# SCH_GPS.net
KiCad netlist of a schematic drawn in EasyEDA
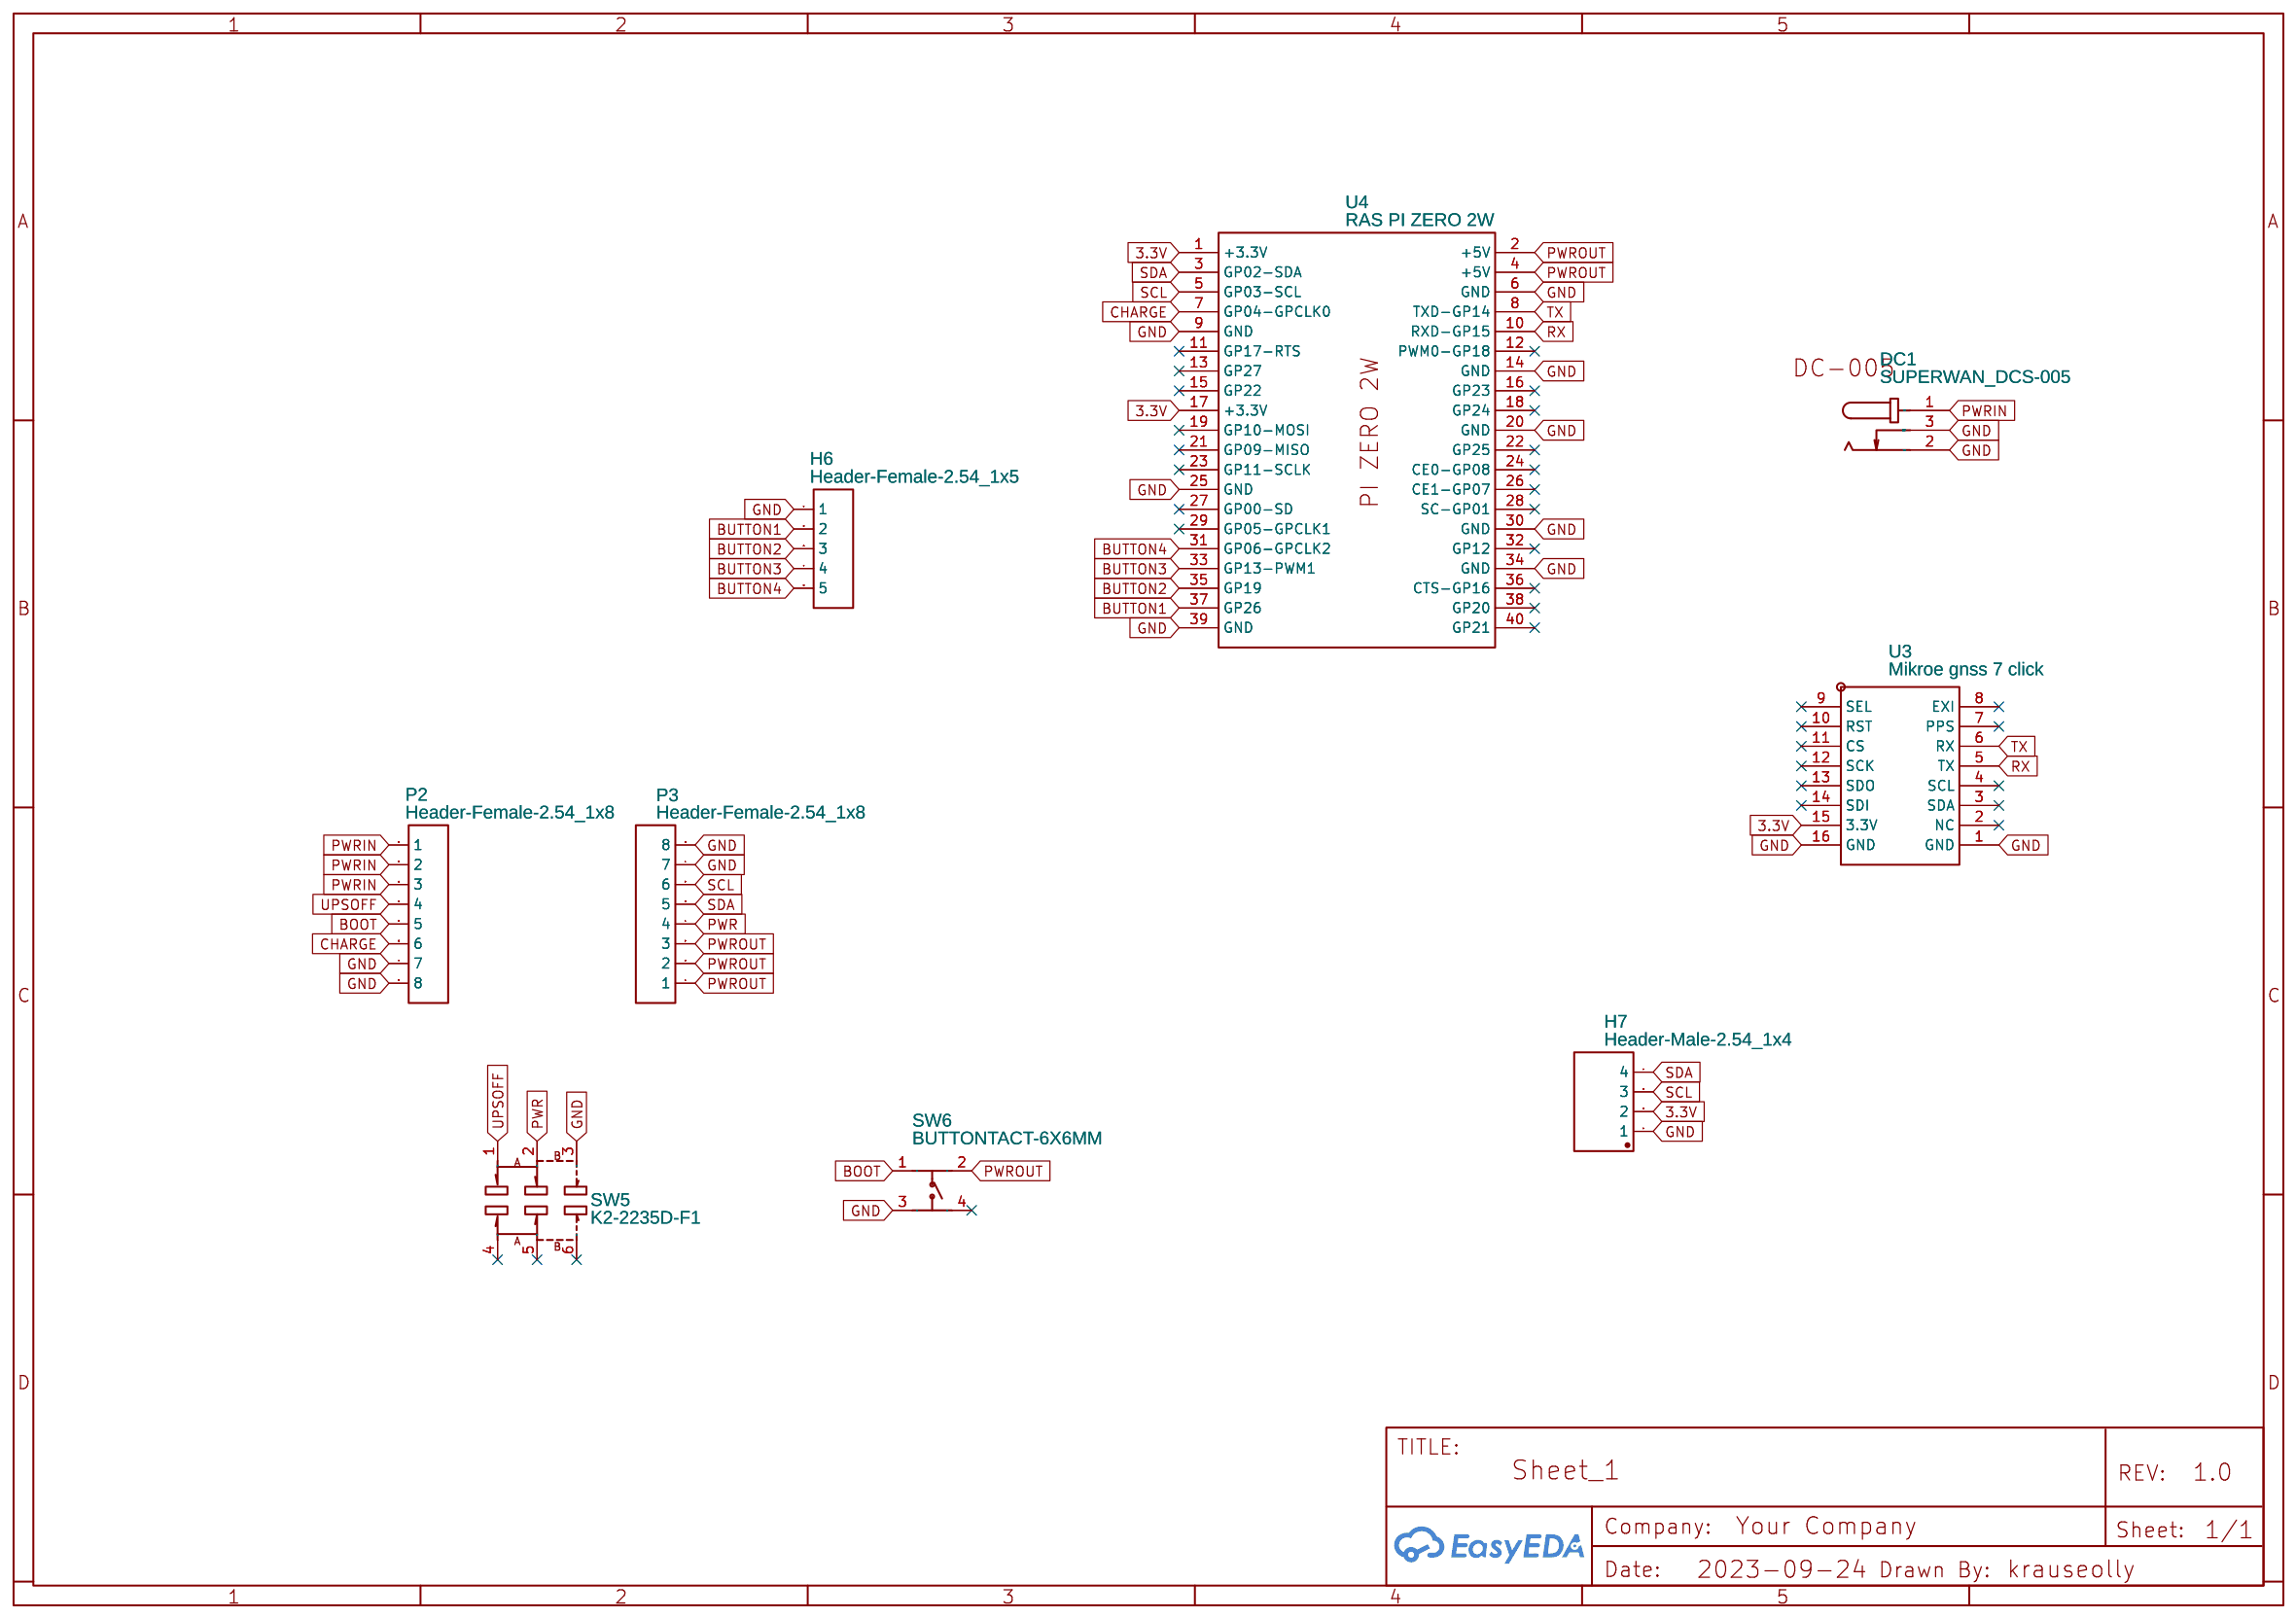
[diagram p0: PI + Power]
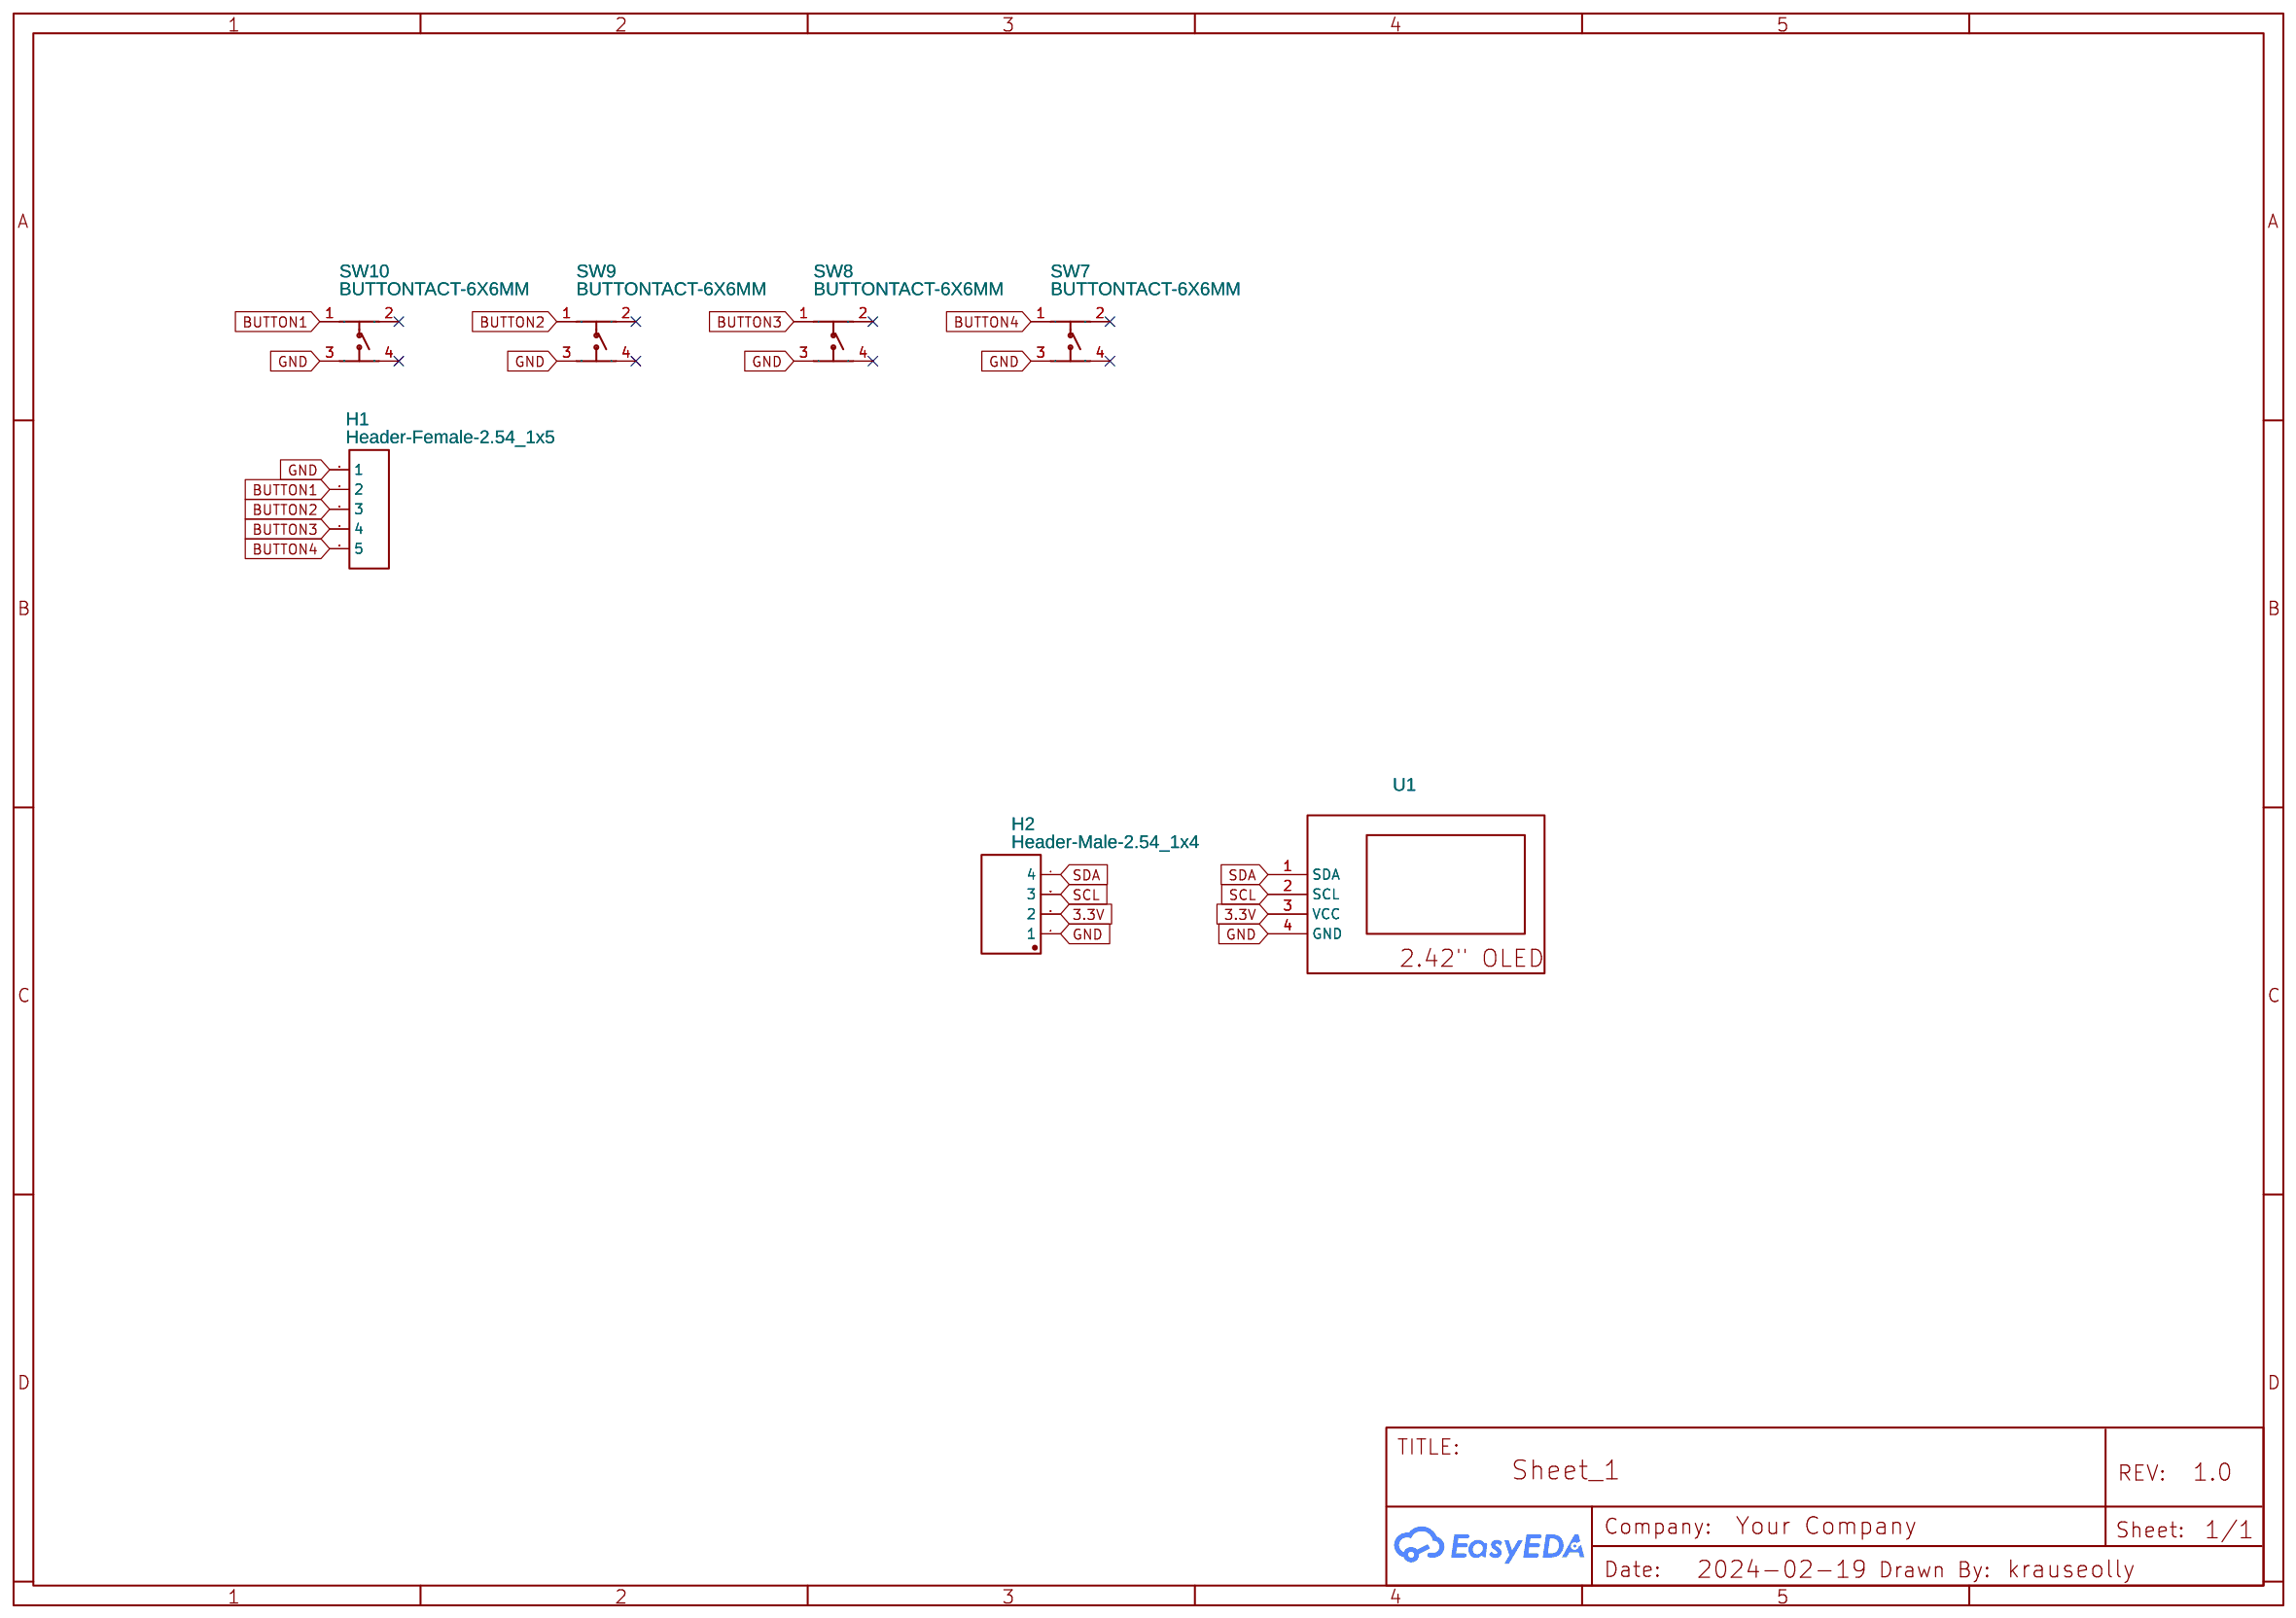
[diagram p1: Screen + Buttons]

(export (version "E")
  (design (tool "Eeschema 10.0.6"))
  (components
    (comp (ref "DC1")
      (value "SUPERWAN_DCS-005")
      (fields (field (name "Manufacturer Part") "DCS-005") (field (name "Manufacturer") "Tongxuan Store"))
      (libsource (lib "") (part "SUPERWAN_DCS-005"))
    )
    (comp (ref "H6")
      (value "Header-Female-2.54_1x5")
      (fields (field (name "Manufacturer Part") "2.54-1*5P母") (field (name "Manufacturer") "BOOMELE(博穆精密)"))
      (libsource (lib "") (part "Header-Female-2.54_1x5"))
    )
    (comp (ref "H7")
      (value "Header-Male-2.54_1x4")
      (fields (field (name "Manufacturer Part") "B-2100S04P-A110") (field (name "Manufacturer") "Ckmtw(灿科盟)"))
      (libsource (lib "") (part "Header-Male-2.54_1x4"))
    )
    (comp (ref "P2")
      (value "Header-Female-2.54_1x8")
      (fields (field (name "Manufacturer Part") "2.54-1*8P母环保") (field (name "Manufacturer") "BOOMELE(博穆精密)"))
      (libsource (lib "") (part "Header-Female-2.54_1x8_1"))
    )
    (comp (ref "P3")
      (value "Header-Female-2.54_1x8")
      (fields (field (name "Manufacturer Part") "2.54-1*8P母环保") (field (name "Manufacturer") "BOOMELE(博穆精密)"))
      (libsource (lib "") (part "Header-Female-2.54_1x8"))
    )
    (comp (ref "SW5")
      (value "K2-2235D-F1")
      (fields (field (name "Manufacturer Part") "K3-2235D-K1") (field (name "Manufacturer") "韩国韩荣"))
      (libsource (lib "") (part "K2-2235D-F1"))
    )
    (comp (ref "SW6")
      (value "BUTTONTACT-6X6MM")
      (fields (field (name "Manufacturer Part") "Buttontact-6x6mm"))
      (libsource (lib "") (part "BUTTONTACT-6X6MM"))
    )
    (comp (ref "U3")
      (value "Mikroe gnss 7 click")
      (fields (field (name "Manufacturer Part") "GNSS 7 CLICK") (field (name "Manufacturer") "MIKROE"))
      (libsource (lib "") (part "Mikroe gnss 7 click"))
    )
    (comp (ref "U4")
      (value "RAS PI ZERO 2W")
      (fields (field (name "Manufacturer Part") "RASPBERRY PI"))
      (libsource (lib "") (part "RAS PI ZERO 2W"))
    )
    (comp (ref "H1")
      (value "Header-Female-2.54_1x5")
      (fields (field (name "Manufacturer Part") "2.54-1*5P母") (field (name "Manufacturer") "BOOMELE(博穆精密)"))
      (libsource (lib "") (part "Header-Female-2.54_1x5"))
    )
    (comp (ref "H2")
      (value "Header-Male-2.54_1x4")
      (fields (field (name "Manufacturer Part") "B-2100S04P-A110") (field (name "Manufacturer") "Ckmtw(灿科盟)"))
      (libsource (lib "") (part "Header-Male-2.54_1x4"))
    )
    (comp (ref "SW7")
      (value "BUTTONTACT-6X6MM")
      (fields (field (name "Manufacturer Part") "Buttontact-6x6mm"))
      (libsource (lib "") (part "BUTTONTACT-6X6MM"))
    )
    (comp (ref "SW8")
      (value "BUTTONTACT-6X6MM")
      (fields (field (name "Manufacturer Part") "Buttontact-6x6mm"))
      (libsource (lib "") (part "BUTTONTACT-6X6MM"))
    )
    (comp (ref "SW9")
      (value "BUTTONTACT-6X6MM")
      (fields (field (name "Manufacturer Part") "Buttontact-6x6mm"))
      (libsource (lib "") (part "BUTTONTACT-6X6MM"))
    )
    (comp (ref "SW10")
      (value "BUTTONTACT-6X6MM")
      (fields (field (name "Manufacturer Part") "Buttontact-6x6mm"))
      (libsource (lib "") (part "BUTTONTACT-6X6MM"))
    )
    (comp (ref "U1")
      (value "NO")
      (fields (field (name "Manufacturer Part") "MONOCHROME 2.42\" 128X64 OLED SSD1309"))
      (libsource (lib "") (part "2.42 OLED (SSD1309, I2C) ZOS"))
    )
  )
  (nets
    (net (code "1") (name "3.3V") (class "Default")
      (node (ref "H2") (pin "2") (pinfunction "2_2") (pintype "unspecified"))
      (node (ref "H7") (pin "2") (pinfunction "2_2") (pintype "unspecified"))
      (node (ref "U1") (pin "3") (pinfunction "VCC_3") (pintype "unspecified"))
      (node (ref "U3") (pin "15") (pinfunction "3.3V_15") (pintype "unspecified"))
      (node (ref "U4") (pin "1") (pinfunction "+3.3V_1") (pintype "unspecified"))
      (node (ref "U4") (pin "17") (pinfunction "+3.3V_17") (pintype "unspecified"))
    )
    (net (code "2") (name "BOOT") (class "Default")
      (node (ref "P2") (pin "5") (pinfunction "5_5") (pintype "input"))
      (node (ref "SW6") (pin "1") (pinfunction "A_1") (pintype "unspecified"))
    )
    (net (code "3") (name "BUTTON1") (class "Default")
      (node (ref "H1") (pin "2") (pinfunction "2_2") (pintype "input"))
      (node (ref "H6") (pin "2") (pinfunction "2_2") (pintype "input"))
      (node (ref "SW10") (pin "1") (pinfunction "A_1") (pintype "unspecified"))
      (node (ref "U4") (pin "37") (pinfunction "GP26_37") (pintype "unspecified"))
    )
    (net (code "4") (name "BUTTON2") (class "Default")
      (node (ref "H1") (pin "3") (pinfunction "3_3") (pintype "input"))
      (node (ref "H6") (pin "3") (pinfunction "3_3") (pintype "input"))
      (node (ref "SW9") (pin "1") (pinfunction "A_1") (pintype "unspecified"))
      (node (ref "U4") (pin "35") (pinfunction "GP19_35") (pintype "unspecified"))
    )
    (net (code "5") (name "BUTTON3") (class "Default")
      (node (ref "H1") (pin "4") (pinfunction "4_4") (pintype "input"))
      (node (ref "H6") (pin "4") (pinfunction "4_4") (pintype "input"))
      (node (ref "SW8") (pin "1") (pinfunction "A_1") (pintype "unspecified"))
      (node (ref "U4") (pin "33") (pinfunction "GP13-PWM1_33") (pintype "unspecified"))
    )
    (net (code "6") (name "BUTTON4") (class "Default")
      (node (ref "H1") (pin "5") (pinfunction "5_5") (pintype "input"))
      (node (ref "H6") (pin "5") (pinfunction "5_5") (pintype "input"))
      (node (ref "SW7") (pin "1") (pinfunction "A_1") (pintype "unspecified"))
      (node (ref "U4") (pin "31") (pinfunction "GP06-GPCLK2_31") (pintype "unspecified"))
    )
    (net (code "7") (name "CHARGE") (class "Default")
      (node (ref "P2") (pin "6") (pinfunction "6_6") (pintype "input"))
      (node (ref "U4") (pin "7") (pinfunction "GP04-GPCLK0_7") (pintype "unspecified"))
    )
    (net (code "8") (name "GND") (class "Default")
      (node (ref "DC1") (pin "2") (pinfunction "SLEEVE_(-)_2") (pintype "unspecified"))
      (node (ref "DC1") (pin "3") (pinfunction "INSERT_DETECTION_3") (pintype "unspecified"))
      (node (ref "H1") (pin "1") (pinfunction "1_1") (pintype "input"))
      (node (ref "H2") (pin "1") (pinfunction "1_1") (pintype "unspecified"))
      (node (ref "H6") (pin "1") (pinfunction "1_1") (pintype "input"))
      (node (ref "H7") (pin "1") (pinfunction "1_1") (pintype "unspecified"))
      (node (ref "P2") (pin "7") (pinfunction "7_7") (pintype "input"))
      (node (ref "P2") (pin "8") (pinfunction "8_8") (pintype "input"))
      (node (ref "P3") (pin "7") (pinfunction "7_7") (pintype "input"))
      (node (ref "P3") (pin "8") (pinfunction "8_8") (pintype "input"))
      (node (ref "SW10") (pin "3") (pinfunction "C_3") (pintype "unspecified"))
      (node (ref "SW5") (pin "3") (pinfunction "3_3") (pintype "unspecified"))
      (node (ref "SW6") (pin "3") (pinfunction "C_3") (pintype "unspecified"))
      (node (ref "SW7") (pin "3") (pinfunction "C_3") (pintype "unspecified"))
      (node (ref "SW8") (pin "3") (pinfunction "C_3") (pintype "unspecified"))
      (node (ref "SW9") (pin "3") (pinfunction "C_3") (pintype "unspecified"))
      (node (ref "U1") (pin "4") (pinfunction "GND_4") (pintype "unspecified"))
      (node (ref "U3") (pin "1") (pinfunction "GND_1") (pintype "unspecified"))
      (node (ref "U3") (pin "16") (pinfunction "GND_16") (pintype "unspecified"))
      (node (ref "U4") (pin "14") (pinfunction "GND_14") (pintype "unspecified"))
      (node (ref "U4") (pin "20") (pinfunction "GND_20") (pintype "unspecified"))
      (node (ref "U4") (pin "25") (pinfunction "GND_25") (pintype "unspecified"))
      (node (ref "U4") (pin "30") (pinfunction "GND_30") (pintype "unspecified"))
      (node (ref "U4") (pin "34") (pinfunction "GND_34") (pintype "unspecified"))
      (node (ref "U4") (pin "39") (pinfunction "GND_39") (pintype "unspecified"))
      (node (ref "U4") (pin "6") (pinfunction "GND_6") (pintype "unspecified"))
      (node (ref "U4") (pin "9") (pinfunction "GND_9") (pintype "unspecified"))
    )
    (net (code "9") (name "PWR") (class "Default")
      (node (ref "P3") (pin "4") (pinfunction "4_4") (pintype "input"))
      (node (ref "SW5") (pin "2") (pinfunction "2_2") (pintype "unspecified"))
    )
    (net (code "10") (name "PWRIN") (class "Default")
      (node (ref "DC1") (pin "1") (pinfunction "TIP_(+)_1") (pintype "unspecified"))
      (node (ref "P2") (pin "1") (pinfunction "1_1") (pintype "input"))
      (node (ref "P2") (pin "2") (pinfunction "2_2") (pintype "input"))
      (node (ref "P2") (pin "3") (pinfunction "3_3") (pintype "input"))
    )
    (net (code "11") (name "PWROUT") (class "Default")
      (node (ref "P3") (pin "1") (pinfunction "1_1") (pintype "input"))
      (node (ref "P3") (pin "2") (pinfunction "2_2") (pintype "input"))
      (node (ref "P3") (pin "3") (pinfunction "3_3") (pintype "input"))
      (node (ref "SW6") (pin "2") (pinfunction "B_2") (pintype "unspecified"))
      (node (ref "U4") (pin "2") (pinfunction "+5V_2") (pintype "unspecified"))
      (node (ref "U4") (pin "4") (pinfunction "+5V_4") (pintype "unspecified"))
    )
    (net (code "12") (name "RX") (class "Default")
      (node (ref "U3") (pin "5") (pinfunction "TX_5") (pintype "unspecified"))
      (node (ref "U4") (pin "10") (pinfunction "RXD-GP15_10") (pintype "unspecified"))
    )
    (net (code "13") (name "SCL") (class "Default")
      (node (ref "H2") (pin "3") (pinfunction "3_3") (pintype "unspecified"))
      (node (ref "H7") (pin "3") (pinfunction "3_3") (pintype "unspecified"))
      (node (ref "P3") (pin "6") (pinfunction "6_6") (pintype "input"))
      (node (ref "U1") (pin "2") (pinfunction "SCL_2") (pintype "unspecified"))
      (node (ref "U4") (pin "5") (pinfunction "GP03-SCL_5") (pintype "unspecified"))
    )
    (net (code "14") (name "SDA") (class "Default")
      (node (ref "H2") (pin "4") (pinfunction "4_4") (pintype "unspecified"))
      (node (ref "H7") (pin "4") (pinfunction "4_4") (pintype "unspecified"))
      (node (ref "P3") (pin "5") (pinfunction "5_5") (pintype "input"))
      (node (ref "U1") (pin "1") (pinfunction "SDA_1") (pintype "unspecified"))
      (node (ref "U4") (pin "3") (pinfunction "GP02-SDA_3") (pintype "unspecified"))
    )
    (net (code "15") (name "TX") (class "Default")
      (node (ref "U3") (pin "6") (pinfunction "RX_6") (pintype "unspecified"))
      (node (ref "U4") (pin "8") (pinfunction "TXD-GP14_8") (pintype "unspecified"))
    )
    (net (code "16") (name "UPSOFF") (class "Default")
      (node (ref "P2") (pin "4") (pinfunction "4_4") (pintype "input"))
      (node (ref "SW5") (pin "1") (pinfunction "1_1") (pintype "unspecified"))
    )
    (net (code "17") (name "unconnected-(SW5-Pad4)") (class "Default")
      (node (ref "SW5") (pin "4") (pinfunction "4_4") (pintype "unspecified+no_connect"))
    )
    (net (code "18") (name "unconnected-(SW5-Pad5)") (class "Default")
      (node (ref "SW5") (pin "5") (pinfunction "5_5") (pintype "unspecified+no_connect"))
    )
    (net (code "19") (name "unconnected-(SW5-Pad6)") (class "Default")
      (node (ref "SW5") (pin "6") (pinfunction "6_6") (pintype "unspecified+no_connect"))
    )
    (net (code "20") (name "unconnected-(SW6-D-Pad4)") (class "Default")
      (node (ref "SW6") (pin "4") (pinfunction "D_4") (pintype "unspecified+no_connect"))
    )
    (net (code "21") (name "unconnected-(SW7-B-Pad2)") (class "Default")
      (node (ref "SW7") (pin "2") (pinfunction "B_2") (pintype "unspecified+no_connect"))
    )
    (net (code "22") (name "unconnected-(SW7-D-Pad4)") (class "Default")
      (node (ref "SW7") (pin "4") (pinfunction "D_4") (pintype "unspecified+no_connect"))
    )
    (net (code "23") (name "unconnected-(SW8-B-Pad2)") (class "Default")
      (node (ref "SW8") (pin "2") (pinfunction "B_2") (pintype "unspecified+no_connect"))
    )
    (net (code "24") (name "unconnected-(SW8-D-Pad4)") (class "Default")
      (node (ref "SW8") (pin "4") (pinfunction "D_4") (pintype "unspecified+no_connect"))
    )
    (net (code "25") (name "unconnected-(SW9-B-Pad2)") (class "Default")
      (node (ref "SW9") (pin "2") (pinfunction "B_2") (pintype "unspecified+no_connect"))
    )
    (net (code "26") (name "unconnected-(SW9-D-Pad4)") (class "Default")
      (node (ref "SW9") (pin "4") (pinfunction "D_4") (pintype "unspecified+no_connect"))
    )
    (net (code "27") (name "unconnected-(SW10-B-Pad2)") (class "Default")
      (node (ref "SW10") (pin "2") (pinfunction "B_2") (pintype "unspecified+no_connect"))
    )
    (net (code "28") (name "unconnected-(SW10-D-Pad4)") (class "Default")
      (node (ref "SW10") (pin "4") (pinfunction "D_4") (pintype "unspecified+no_connect"))
    )
    (net (code "29") (name "unconnected-(U3-CS-Pad11)") (class "Default")
      (node (ref "U3") (pin "11") (pinfunction "CS_11") (pintype "unspecified+no_connect"))
    )
    (net (code "30") (name "unconnected-(U3-EXI-Pad8)") (class "Default")
      (node (ref "U3") (pin "8") (pinfunction "EXI_8") (pintype "unspecified+no_connect"))
    )
    (net (code "31") (name "unconnected-(U3-NC-Pad2)") (class "Default")
      (node (ref "U3") (pin "2") (pinfunction "NC_2") (pintype "unspecified+no_connect"))
    )
    (net (code "32") (name "unconnected-(U3-PPS-Pad7)") (class "Default")
      (node (ref "U3") (pin "7") (pinfunction "PPS_7") (pintype "unspecified+no_connect"))
    )
    (net (code "33") (name "unconnected-(U3-RST-Pad10)") (class "Default")
      (node (ref "U3") (pin "10") (pinfunction "RST_10") (pintype "unspecified+no_connect"))
    )
    (net (code "34") (name "unconnected-(U3-SCK-Pad12)") (class "Default")
      (node (ref "U3") (pin "12") (pinfunction "SCK_12") (pintype "unspecified+no_connect"))
    )
    (net (code "35") (name "unconnected-(U3-SCL-Pad4)") (class "Default")
      (node (ref "U3") (pin "4") (pinfunction "SCL_4") (pintype "unspecified+no_connect"))
    )
    (net (code "36") (name "unconnected-(U3-SDA-Pad3)") (class "Default")
      (node (ref "U3") (pin "3") (pinfunction "SDA_3") (pintype "unspecified+no_connect"))
    )
    (net (code "37") (name "unconnected-(U3-SDI-Pad14)") (class "Default")
      (node (ref "U3") (pin "14") (pinfunction "SDI_14") (pintype "unspecified+no_connect"))
    )
    (net (code "38") (name "unconnected-(U3-SDO-Pad13)") (class "Default")
      (node (ref "U3") (pin "13") (pinfunction "SDO_13") (pintype "unspecified+no_connect"))
    )
    (net (code "39") (name "unconnected-(U3-SEL-Pad9)") (class "Default")
      (node (ref "U3") (pin "9") (pinfunction "SEL_9") (pintype "unspecified+no_connect"))
    )
    (net (code "40") (name "unconnected-(U4-CE0-GP08-Pad24)") (class "Default")
      (node (ref "U4") (pin "24") (pinfunction "CE0-GP08_24") (pintype "unspecified+no_connect"))
    )
    (net (code "41") (name "unconnected-(U4-CE1-GP07-Pad26)") (class "Default")
      (node (ref "U4") (pin "26") (pinfunction "CE1-GP07_26") (pintype "unspecified+no_connect"))
    )
    (net (code "42") (name "unconnected-(U4-CTS-GP16-Pad36)") (class "Default")
      (node (ref "U4") (pin "36") (pinfunction "CTS-GP16_36") (pintype "unspecified+no_connect"))
    )
    (net (code "43") (name "unconnected-(U4-GP00-SD-Pad27)") (class "Default")
      (node (ref "U4") (pin "27") (pinfunction "GP00-SD_27") (pintype "unspecified+no_connect"))
    )
    (net (code "44") (name "unconnected-(U4-GP05-GPCLK1-Pad29)") (class "Default")
      (node (ref "U4") (pin "29") (pinfunction "GP05-GPCLK1_29") (pintype "unspecified+no_connect"))
    )
    (net (code "45") (name "unconnected-(U4-GP09-MISO-Pad21)") (class "Default")
      (node (ref "U4") (pin "21") (pinfunction "GP09-MISO_21") (pintype "unspecified+no_connect"))
    )
    (net (code "46") (name "unconnected-(U4-GP10-MOSI-Pad19)") (class "Default")
      (node (ref "U4") (pin "19") (pinfunction "GP10-MOSI_19") (pintype "unspecified+no_connect"))
    )
    (net (code "47") (name "unconnected-(U4-GP11-SCLK-Pad23)") (class "Default")
      (node (ref "U4") (pin "23") (pinfunction "GP11-SCLK_23") (pintype "unspecified+no_connect"))
    )
    (net (code "48") (name "unconnected-(U4-GP12-Pad32)") (class "Default")
      (node (ref "U4") (pin "32") (pinfunction "GP12_32") (pintype "unspecified+no_connect"))
    )
    (net (code "49") (name "unconnected-(U4-GP17-RTS-Pad11)") (class "Default")
      (node (ref "U4") (pin "11") (pinfunction "GP17-RTS_11") (pintype "unspecified+no_connect"))
    )
    (net (code "50") (name "unconnected-(U4-GP20-Pad38)") (class "Default")
      (node (ref "U4") (pin "38") (pinfunction "GP20_38") (pintype "unspecified+no_connect"))
    )
    (net (code "51") (name "unconnected-(U4-GP21-Pad40)") (class "Default")
      (node (ref "U4") (pin "40") (pinfunction "GP21_40") (pintype "unspecified+no_connect"))
    )
    (net (code "52") (name "unconnected-(U4-GP22-Pad15)") (class "Default")
      (node (ref "U4") (pin "15") (pinfunction "GP22_15") (pintype "unspecified+no_connect"))
    )
    (net (code "53") (name "unconnected-(U4-GP23-Pad16)") (class "Default")
      (node (ref "U4") (pin "16") (pinfunction "GP23_16") (pintype "unspecified+no_connect"))
    )
    (net (code "54") (name "unconnected-(U4-GP24-Pad18)") (class "Default")
      (node (ref "U4") (pin "18") (pinfunction "GP24_18") (pintype "unspecified+no_connect"))
    )
    (net (code "55") (name "unconnected-(U4-GP25-Pad22)") (class "Default")
      (node (ref "U4") (pin "22") (pinfunction "GP25_22") (pintype "unspecified+no_connect"))
    )
    (net (code "56") (name "unconnected-(U4-GP27-Pad13)") (class "Default")
      (node (ref "U4") (pin "13") (pinfunction "GP27_13") (pintype "unspecified+no_connect"))
    )
    (net (code "57") (name "unconnected-(U4-PWM0-GP18-Pad12)") (class "Default")
      (node (ref "U4") (pin "12") (pinfunction "PWM0-GP18_12") (pintype "unspecified+no_connect"))
    )
    (net (code "58") (name "unconnected-(U4-SC-GP01-Pad28)") (class "Default")
      (node (ref "U4") (pin "28") (pinfunction "SC-GP01_28") (pintype "unspecified+no_connect"))
    )
  )
)
